# SOC_nRF52832.net
KiCad netlist of a schematic drawn in Altium Designer
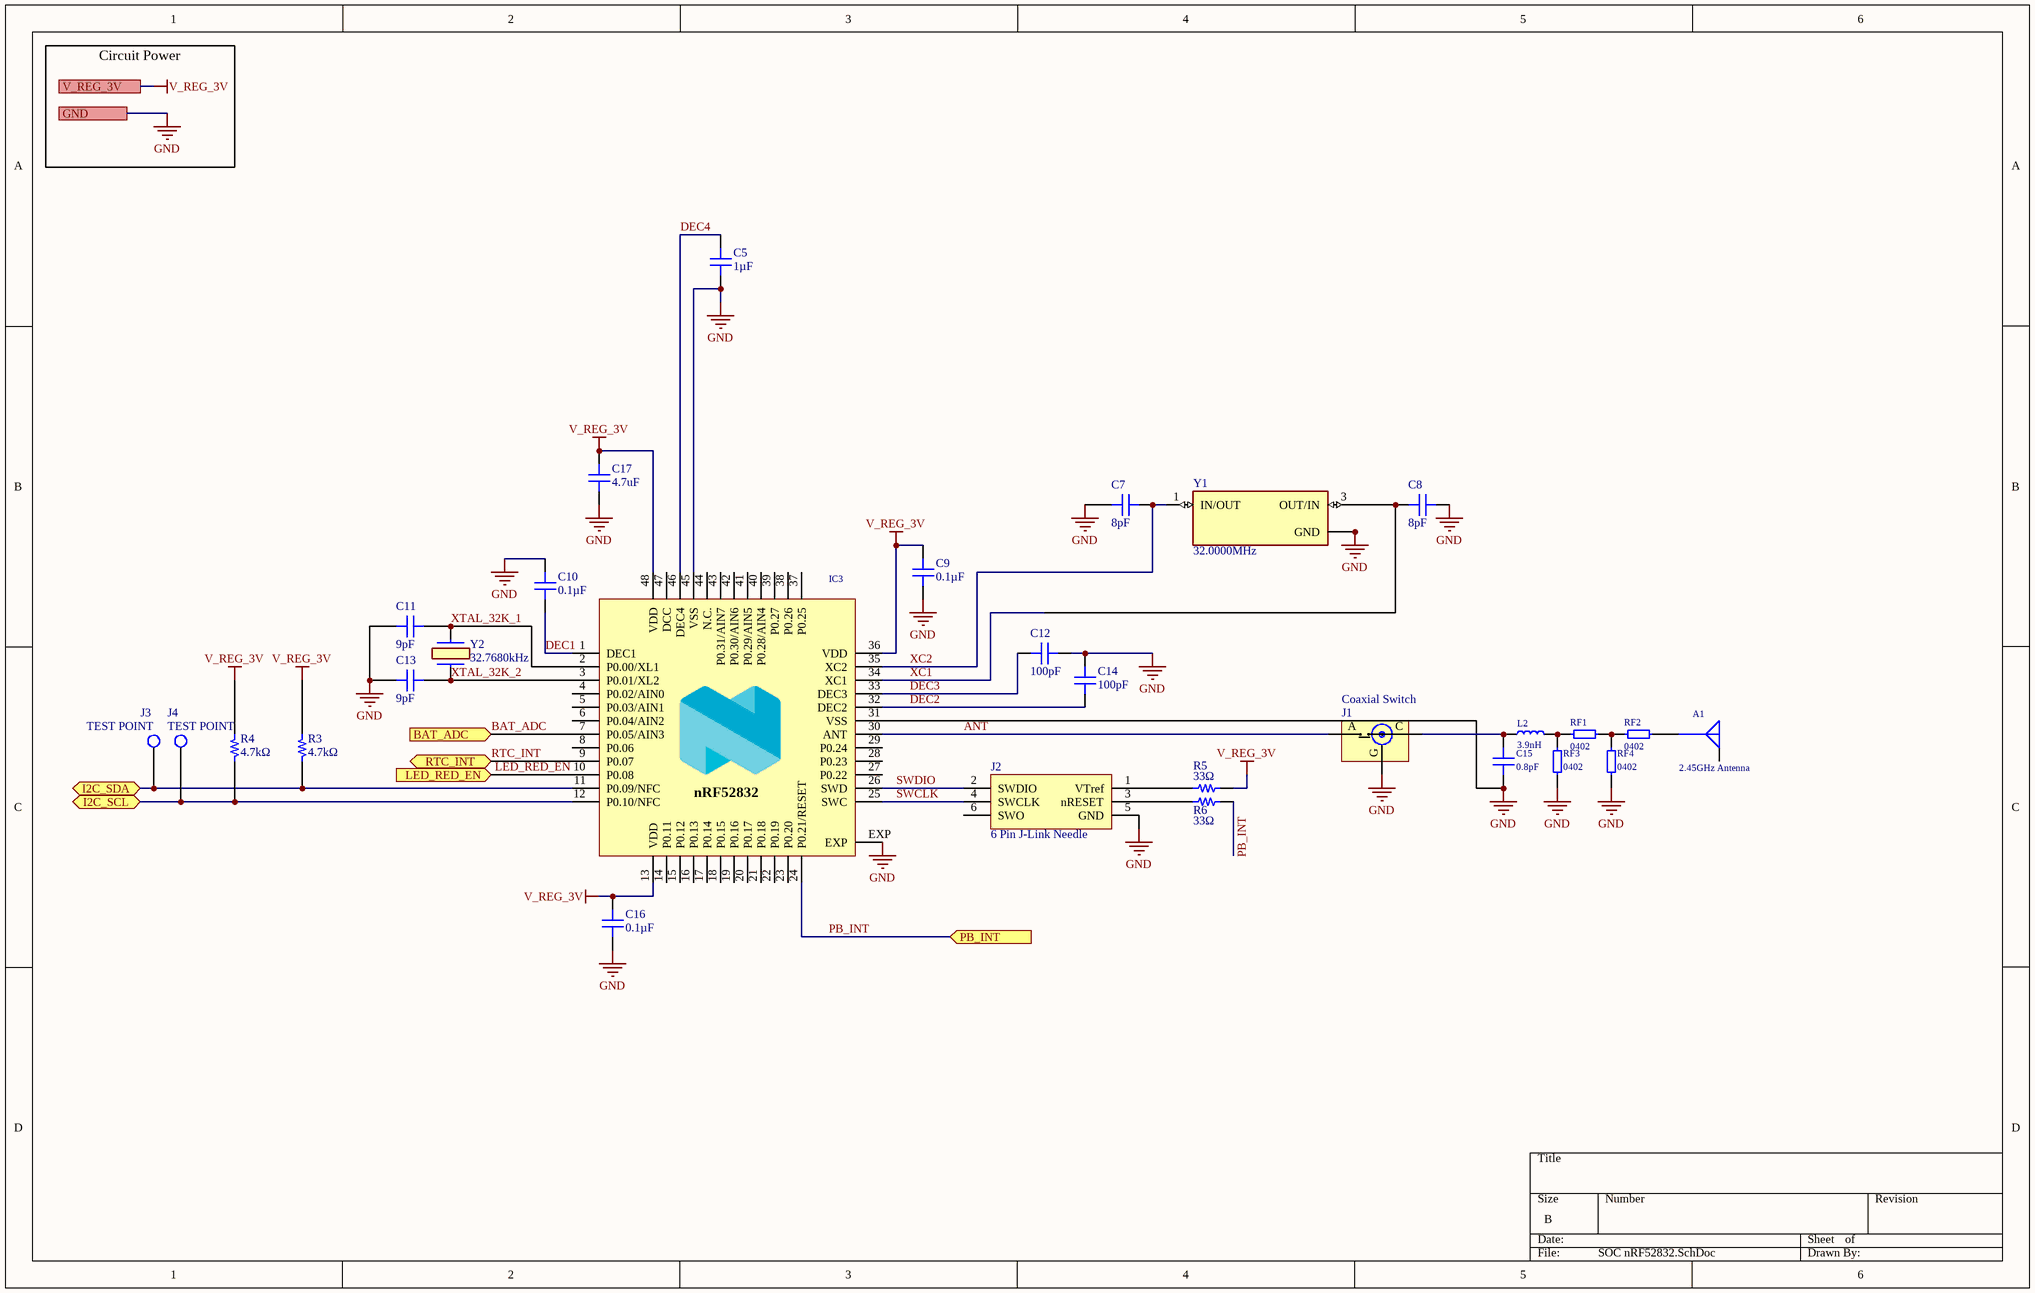
[diagram p0: SOC nRF52832.SchDoc]

(export (version "E")
  (design (tool "Eeschema 10.0.6"))
  (components
    (comp (ref "A1")
      (value "2.45GHz Antenna")
      (footprint "FRACTUS ANTENNAS FR01-S1-N-0-102")
      (description "COMPACT REACH XTEND - 102")
      (fields (field (name "MANUFACTURER") "Ignion"))
      (libsource (lib "MVVVMAltiumDatabase") (part "Basic Antenna"))
    )
    (comp (ref "C5")
      (value "1µF")
      (footprint "CAP 0402_1005 RF")
      (description "CAP CER 1UF 10V X7S 0402")
      (fields (field (name "MANUFACTURER") "Murata Electronics") (field (name "VOLTAGE") "10V"))
      (libsource (lib "MVVVMAltiumDatabase") (part "Capacitor"))
    )
    (comp (ref "C7")
      (value "8pF")
      (footprint "CAP 0402_1005")
      (description "CAP CER 8PF 50V NPO 0402")
      (fields (field (name "MANUFACTURER") "Walsin") (field (name "VOLTAGE") "50V"))
      (libsource (lib "MVVVMAltiumDatabase") (part "Capacitor"))
    )
    (comp (ref "C8")
      (value "8pF")
      (footprint "CAP 0402_1005")
      (description "CAP CER 8PF 50V NPO 0402")
      (fields (field (name "MANUFACTURER") "Walsin") (field (name "VOLTAGE") "50V"))
      (libsource (lib "MVVVMAltiumDatabase") (part "Capacitor"))
    )
    (comp (ref "C9")
      (value "0.1µF")
      (footprint "CAP 0402_1005")
      (description "CAP CER 0.1UF 16V X7R 0402")
      (fields (field (name "MANUFACTURER") "KEMET") (field (name "VOLTAGE") "16V"))
      (libsource (lib "MVVVMAltiumDatabase") (part "Capacitor"))
    )
    (comp (ref "C10")
      (value "0.1µF")
      (footprint "CAP 0402_1005")
      (description "CAP CER 0.1UF 16V X7R 0402")
      (fields (field (name "MANUFACTURER") "KEMET") (field (name "VOLTAGE") "16V"))
      (libsource (lib "MVVVMAltiumDatabase") (part "Capacitor"))
    )
    (comp (ref "C11")
      (value "9pF")
      (footprint "CAP 0402_1005")
      (description "CAP CER 9PF 50V NPO 0402")
      (fields (field (name "MANUFACTURER") "Walsin") (field (name "VOLTAGE") "50V"))
      (libsource (lib "MVVVMAltiumDatabase") (part "Capacitor"))
    )
    (comp (ref "C12")
      (value "100pF")
      (footprint "CAP 0402_1005")
      (description "CAP CER 100PF 16V C0G/NP0 0402")
      (fields (field (name "MANUFACTURER") "KEMET") (field (name "VOLTAGE") "16V"))
      (libsource (lib "MVVVMAltiumDatabase") (part "Capacitor"))
    )
    (comp (ref "C13")
      (value "9pF")
      (footprint "CAP 0402_1005")
      (description "CAP CER 9PF 50V NPO 0402")
      (fields (field (name "MANUFACTURER") "Walsin") (field (name "VOLTAGE") "50V"))
      (libsource (lib "MVVVMAltiumDatabase") (part "Capacitor"))
    )
    (comp (ref "C14")
      (value "100pF")
      (footprint "CAP 0402_1005")
      (description "CAP CER 100PF 16V C0G/NP0 0402")
      (fields (field (name "MANUFACTURER") "KEMET") (field (name "VOLTAGE") "16V"))
      (libsource (lib "MVVVMAltiumDatabase") (part "Capacitor"))
    )
    (comp (ref "C15")
      (value "0.8pF")
      (footprint "CAP 0603_1608")
      (description "CAP CER 0.8PF 50V NP0  0603")
      (fields (field (name "MANUFACTURER") "Walsin") (field (name "VOLTAGE") "50V"))
      (libsource (lib "MVVVMAltiumDatabase") (part "Capacitor"))
    )
    (comp (ref "C16")
      (value "0.1µF")
      (footprint "CAP 0402_1005")
      (description "CAP CER 0.1UF 16V X7R 0402")
      (fields (field (name "MANUFACTURER") "KEMET") (field (name "VOLTAGE") "16V"))
      (libsource (lib "MVVVMAltiumDatabase") (part "Capacitor"))
    )
    (comp (ref "C17")
      (value "4.7uF")
      (footprint "CAP 0402_1005")
      (description "CAP CER 8PF 50V NPO 0402")
      (fields (field (name "MANUFACTURER") "Samsung Electro-Mechanics") (field (name "VOLTAGE") "10V"))
      (libsource (lib "MVVVMAltiumDatabase") (part "Capacitor"))
    )
    (comp (ref "IC3")
      (value "RF SoC")
      (footprint "NORDIC QFN-48")
      (description "IC RF TXRX+MCU BLUETOOTH 48VFQFN")
      (fields (field (name "MANUFACTURER") "Nordic Semiconductor"))
      (libsource (lib "MVVVMAltiumDatabase") (part "NORDIC NRF52832 QFN48"))
    )
    (comp (ref "J1")
      (value "Coaxial Switch")
      (footprint "HIROSE MS-156HF(01)")
      (description "CONN COAX SWITCH RCPT STR 50OHM")
      (fields (field (name "MANUFACTURER") "Hirose Electric Co Ltd"))
      (libsource (lib "MVVVMAltiumDatabase") (part "HIROSE MS-156HF(01)"))
    )
    (comp (ref "J2")
      (value "6 Pin J-Link Needle")
      (footprint "J-LINK 6-PIN NEEDLE")
      (libsource (lib "MVVVMAltiumDatabase") (part "6 Pin"))
    )
    (comp (ref "J3")
      (value "TEST POINT")
      (footprint "TEST POINT")
      (libsource (lib "MVVVMAltiumDatabase") (part "TEST POINT"))
    )
    (comp (ref "J4")
      (value "TEST POINT")
      (footprint "TEST POINT")
      (libsource (lib "MVVVMAltiumDatabase") (part "TEST POINT"))
    )
    (comp (ref "L2")
      (value "3.9nH")
      (footprint "IND 0402_1005")
      (description "FIXED IND 3.9NH 250MA 450MOHM SM")
      (fields (field (name "MANUFACTURER") "KYOCERA AVX") (field (name "TOLERANCE") "±0.1%"))
      (libsource (lib "MVVVMAltiumDatabase") (part "Inductor_2"))
    )
    (comp (ref "R3")
      (value "4.7kΩ")
      (footprint "RES 0402_1005 RF")
      (description "RES SMD 4.7K OHM 1% 1/8W 0402")
      (fields (field (name "MANUFACTURER") "YAGEO") (field (name "TOLERANCE") "±1%"))
      (libsource (lib "MVVVMAltiumDatabase") (part "Resistor"))
    )
    (comp (ref "R4")
      (value "4.7kΩ")
      (footprint "RES 0402_1005 RF")
      (description "RES SMD 4.7K OHM 1% 1/8W 0402")
      (fields (field (name "MANUFACTURER") "YAGEO") (field (name "TOLERANCE") "±1%"))
      (libsource (lib "MVVVMAltiumDatabase") (part "Resistor"))
    )
    (comp (ref "R5")
      (value "33Ω")
      (footprint "RES 0201_0603")
      (description "RES SMD 33 OHM 1% 1/20W 0201")
      (fields (field (name "MANUFACTURER") "Vishay Dale") (field (name "TOLERANCE") "±1%"))
      (libsource (lib "MVVVMAltiumDatabase") (part "Resistor"))
    )
    (comp (ref "R6")
      (value "33Ω")
      (footprint "RES 0201_0603")
      (description "RES SMD 33 OHM 1% 1/20W 0201")
      (fields (field (name "MANUFACTURER") "Vishay Dale") (field (name "TOLERANCE") "±1%"))
      (libsource (lib "MVVVMAltiumDatabase") (part "Resistor"))
    )
    (comp (ref "RF1")
      (value "0402")
      (footprint "0402_1005 RF")
      (description "0402 RF Passive")
      (libsource (lib "MVVVMAltiumDatabase") (part "RF Passive"))
    )
    (comp (ref "RF2")
      (value "0402")
      (footprint "0402_1005 RF")
      (description "0402 RF Passive")
      (libsource (lib "MVVVMAltiumDatabase") (part "RF Passive"))
    )
    (comp (ref "RF3")
      (value "0402")
      (footprint "0402_1005 RF")
      (description "0402 RF Passive")
      (libsource (lib "MVVVMAltiumDatabase") (part "RF Passive"))
    )
    (comp (ref "RF4")
      (value "0402")
      (footprint "0402_1005 RF")
      (description "0402 RF Passive")
      (libsource (lib "MVVVMAltiumDatabase") (part "RF Passive"))
    )
    (comp (ref "Y1")
      (value "32.0000MHz")
      (footprint "ECS 320-8-37B")
      (description "CRYSTAL 32.0000MHZ 8PF SMD")
      (fields (field (name "MANUFACTURER") "ECS") (field (name "TOLERANCE") "±7ppm"))
      (libsource (lib "MVVVMAltiumDatabase") (part "ECS CRYSTAL 320-8-37B"))
    )
    (comp (ref "Y2")
      (value "32.7680kHz")
      (footprint "EPSON FC135R")
      (description "CRYSTAL 32.7680KHZ 9PF SMD")
      (fields (field (name "MANUFACTURER") "EPSON") (field (name "TOLERANCE") "±10ppm"))
      (libsource (lib "MVVVMAltiumDatabase") (part "EPSON CRYSTAL FC135R"))
    )
  )
  (nets
    (net (code "1") (name "/ANT") (class "Default")
      (node (ref "IC3") (pin "30") (pinfunction "ANT_30") (pintype "passive"))
      (node (ref "J1") (pin "A") (pinfunction "A_A") (pintype "passive"))
    )
    (net (code "2") (name "/BAT_ADC") (class "Default")
      (node (ref "IC3") (pin "7") (pinfunction "P0.05/AIN3_7") (pintype "passive"))
    )
    (net (code "3") (name "/DEC1") (class "Default")
      (node (ref "C10") (pin "1") (pinfunction "1_1") (pintype "passive"))
      (node (ref "IC3") (pin "1") (pinfunction "DEC1_1") (pintype "passive"))
    )
    (net (code "4") (name "/DEC2") (class "Default")
      (node (ref "C14") (pin "1") (pinfunction "1_1") (pintype "passive"))
      (node (ref "IC3") (pin "32") (pinfunction "DEC2_32") (pintype "passive"))
    )
    (net (code "5") (name "/DEC3") (class "Default")
      (node (ref "C12") (pin "1") (pinfunction "1_1") (pintype "passive"))
      (node (ref "IC3") (pin "33") (pinfunction "DEC3_33") (pintype "passive"))
    )
    (net (code "6") (name "/DEC4") (class "Default")
      (node (ref "C5") (pin "2") (pinfunction "2_2") (pintype "passive"))
      (node (ref "IC3") (pin "46") (pinfunction "DEC4_46") (pintype "passive"))
    )
    (net (code "7") (name "/I2C_SCL") (class "Default")
      (node (ref "IC3") (pin "12") (pinfunction "P0.10/NFC_12") (pintype "passive"))
      (node (ref "J4") (pin "1") (pinfunction "PAD_1") (pintype "passive"))
      (node (ref "R4") (pin "1") (pinfunction "1_1") (pintype "passive"))
    )
    (net (code "8") (name "/I2C_SDA") (class "Default")
      (node (ref "IC3") (pin "11") (pinfunction "P0.09/NFC_11") (pintype "passive"))
      (node (ref "J3") (pin "1") (pinfunction "PAD_1") (pintype "passive"))
      (node (ref "R3") (pin "1") (pinfunction "1_1") (pintype "passive"))
    )
    (net (code "9") (name "/LED_RED_EN") (class "Default")
      (node (ref "IC3") (pin "10") (pinfunction "P0.08_10") (pintype "passive"))
    )
    (net (code "10") (name "/PB_INT") (class "Default")
      (node (ref "IC3") (pin "24") (pinfunction "P0.21/RESET_24") (pintype "passive"))
      (node (ref "R6") (pin "2") (pinfunction "2_2") (pintype "passive"))
    )
    (net (code "11") (name "/RTC_INT") (class "Default")
      (node (ref "IC3") (pin "9") (pinfunction "P0.07_9") (pintype "passive"))
    )
    (net (code "12") (name "/SWCLK") (class "Default")
      (node (ref "IC3") (pin "25") (pinfunction "SWC_25") (pintype "passive"))
      (node (ref "J2") (pin "4") (pinfunction "SWCLK_4") (pintype "passive"))
    )
    (net (code "13") (name "/SWDIO") (class "Default")
      (node (ref "IC3") (pin "26") (pinfunction "SWD_26") (pintype "passive"))
      (node (ref "J2") (pin "2") (pinfunction "SWDIO_2") (pintype "passive"))
    )
    (net (code "14") (name "/XC1") (class "Default")
      (node (ref "C8") (pin "1") (pinfunction "1_1") (pintype "passive"))
      (node (ref "IC3") (pin "34") (pinfunction "XC1_34") (pintype "passive"))
      (node (ref "Y1") (pin "3") (pinfunction "OUT/IN_3") (pintype "bidirectional"))
    )
    (net (code "15") (name "/XC2") (class "Default")
      (node (ref "C7") (pin "2") (pinfunction "2_2") (pintype "passive"))
      (node (ref "IC3") (pin "35") (pinfunction "XC2_35") (pintype "passive"))
      (node (ref "Y1") (pin "1") (pinfunction "IN/OUT_1") (pintype "bidirectional"))
    )
    (net (code "16") (name "/XTAL_32K_1") (class "Default")
      (node (ref "C11") (pin "2") (pinfunction "2_2") (pintype "passive"))
      (node (ref "IC3") (pin "2") (pinfunction "P0.00/XL1_2") (pintype "passive"))
      (node (ref "Y2") (pin "1") (pinfunction "CRYSTAL_1_1") (pintype "passive"))
    )
    (net (code "17") (name "/XTAL_32K_2") (class "Default")
      (node (ref "C13") (pin "2") (pinfunction "2_2") (pintype "passive"))
      (node (ref "IC3") (pin "3") (pinfunction "P0.01/XL2_3") (pintype "passive"))
      (node (ref "Y2") (pin "2") (pinfunction "CRYSTAL_2_2") (pintype "passive"))
    )
    (net (code "18") (name "GND") (class "Default")
      (node (ref "C10") (pin "2") (pinfunction "2_2") (pintype "passive"))
      (node (ref "C11") (pin "1") (pinfunction "1_1") (pintype "passive"))
      (node (ref "C12") (pin "2") (pinfunction "2_2") (pintype "passive"))
      (node (ref "C13") (pin "1") (pinfunction "1_1") (pintype "passive"))
      (node (ref "C14") (pin "2") (pinfunction "2_2") (pintype "passive"))
      (node (ref "C15") (pin "1") (pinfunction "1_1") (pintype "passive"))
      (node (ref "C16") (pin "1") (pinfunction "1_1") (pintype "passive"))
      (node (ref "C17") (pin "1") (pinfunction "1_1") (pintype "passive"))
      (node (ref "C5") (pin "1") (pinfunction "1_1") (pintype "passive"))
      (node (ref "C7") (pin "1") (pinfunction "1_1") (pintype "passive"))
      (node (ref "C8") (pin "2") (pinfunction "2_2") (pintype "passive"))
      (node (ref "C9") (pin "1") (pinfunction "1_1") (pintype "passive"))
      (node (ref "IC3") (pin "31") (pinfunction "VSS_31") (pintype "passive"))
      (node (ref "IC3") (pin "45") (pinfunction "VSS_45") (pintype "passive"))
      (node (ref "IC3") (pin "EXP") (pinfunction "EXP_EXP") (pintype "passive"))
      (node (ref "J1") (pin "G") (pinfunction "G_G") (pintype "passive"))
      (node (ref "J2") (pin "5") (pinfunction "GND_5") (pintype "passive"))
      (node (ref "RF3") (pin "1") (pinfunction "1_1") (pintype "passive"))
      (node (ref "RF4") (pin "1") (pinfunction "1_1") (pintype "passive"))
      (node (ref "Y1") (pin "2") (pinfunction "GND_2") (pintype "power_in"))
      (node (ref "Y1") (pin "4") (pinfunction "GND_4") (pintype "power_in"))
    )
    (net (code "19") (name "Net-(A1-PadS)") (class "Default")
      (node (ref "A1") (pin "S") (pinfunction "S_S") (pintype "passive"))
      (node (ref "RF2") (pin "2") (pinfunction "2_2") (pintype "passive"))
    )
    (net (code "20") (name "Net-(C15-Pad2)") (class "Default")
      (node (ref "C15") (pin "2") (pinfunction "2_2") (pintype "passive"))
      (node (ref "J1") (pin "C") (pinfunction "C_C") (pintype "passive"))
      (node (ref "L2") (pin "1") (pinfunction "1_1") (pintype "passive"))
    )
    (net (code "21") (name "Net-(J2-VTref)") (class "Default")
      (node (ref "J2") (pin "1") (pinfunction "VTref_1") (pintype "passive"))
      (node (ref "R5") (pin "1") (pinfunction "1_1") (pintype "passive"))
    )
    (net (code "22") (name "Net-(J2-nRESET)") (class "Default")
      (node (ref "J2") (pin "3") (pinfunction "nRESET_3") (pintype "passive"))
      (node (ref "R6") (pin "1") (pinfunction "1_1") (pintype "passive"))
    )
    (net (code "23") (name "Net-(L2-Pad2)") (class "Default")
      (node (ref "L2") (pin "2") (pinfunction "2_2") (pintype "passive"))
      (node (ref "RF1") (pin "1") (pinfunction "1_1") (pintype "passive"))
      (node (ref "RF3") (pin "2") (pinfunction "2_2") (pintype "passive"))
    )
    (net (code "24") (name "Net-(RF1-Pad2)") (class "Default")
      (node (ref "RF1") (pin "2") (pinfunction "2_2") (pintype "passive"))
      (node (ref "RF2") (pin "1") (pinfunction "1_1") (pintype "passive"))
      (node (ref "RF4") (pin "2") (pinfunction "2_2") (pintype "passive"))
    )
    (net (code "25") (name "V_REG_3V") (class "Default")
      (node (ref "C16") (pin "2") (pinfunction "2_2") (pintype "passive"))
      (node (ref "C17") (pin "2") (pinfunction "2_2") (pintype "passive"))
      (node (ref "C9") (pin "2") (pinfunction "2_2") (pintype "passive"))
      (node (ref "IC3") (pin "13") (pinfunction "VDD_13") (pintype "passive"))
      (node (ref "IC3") (pin "36") (pinfunction "VDD_36") (pintype "passive"))
      (node (ref "IC3") (pin "48") (pinfunction "VDD_48") (pintype "passive"))
      (node (ref "R3") (pin "2") (pinfunction "2_2") (pintype "passive"))
      (node (ref "R4") (pin "2") (pinfunction "2_2") (pintype "passive"))
      (node (ref "R5") (pin "2") (pinfunction "2_2") (pintype "passive"))
    )
    (net (code "26") (name "unconnected-(A1-PadG)") (class "Default")
      (node (ref "A1") (pin "G") (pinfunction "G_G") (pintype "passive"))
    )
    (net (code "27") (name "unconnected-(IC3-DCC-Pad47)") (class "Default")
      (node (ref "IC3") (pin "47") (pinfunction "DCC_47") (pintype "passive"))
    )
    (net (code "28") (name "unconnected-(IC3-N.C.-Pad44)") (class "Default")
      (node (ref "IC3") (pin "44") (pinfunction "N.C._44") (pintype "passive"))
    )
    (net (code "29") (name "unconnected-(IC3-P0.02{slash}AIN0-Pad4)") (class "Default")
      (node (ref "IC3") (pin "4") (pinfunction "P0.02/AIN0_4") (pintype "passive"))
    )
    (net (code "30") (name "unconnected-(IC3-P0.03{slash}AIN1-Pad5)") (class "Default")
      (node (ref "IC3") (pin "5") (pinfunction "P0.03/AIN1_5") (pintype "passive"))
    )
    (net (code "31") (name "unconnected-(IC3-P0.04{slash}AIN2-Pad6)") (class "Default")
      (node (ref "IC3") (pin "6") (pinfunction "P0.04/AIN2_6") (pintype "passive"))
    )
    (net (code "32") (name "unconnected-(IC3-P0.06-Pad8)") (class "Default")
      (node (ref "IC3") (pin "8") (pinfunction "P0.06_8") (pintype "passive"))
    )
    (net (code "33") (name "unconnected-(IC3-P0.11-Pad14)") (class "Default")
      (node (ref "IC3") (pin "14") (pinfunction "P0.11_14") (pintype "passive"))
    )
    (net (code "34") (name "unconnected-(IC3-P0.12-Pad15)") (class "Default")
      (node (ref "IC3") (pin "15") (pinfunction "P0.12_15") (pintype "passive"))
    )
    (net (code "35") (name "unconnected-(IC3-P0.13-Pad16)") (class "Default")
      (node (ref "IC3") (pin "16") (pinfunction "P0.13_16") (pintype "passive"))
    )
    (net (code "36") (name "unconnected-(IC3-P0.14-Pad17)") (class "Default")
      (node (ref "IC3") (pin "17") (pinfunction "P0.14_17") (pintype "passive"))
    )
    (net (code "37") (name "unconnected-(IC3-P0.15-Pad18)") (class "Default")
      (node (ref "IC3") (pin "18") (pinfunction "P0.15_18") (pintype "passive"))
    )
    (net (code "38") (name "unconnected-(IC3-P0.16-Pad19)") (class "Default")
      (node (ref "IC3") (pin "19") (pinfunction "P0.16_19") (pintype "passive"))
    )
    (net (code "39") (name "unconnected-(IC3-P0.17-Pad20)") (class "Default")
      (node (ref "IC3") (pin "20") (pinfunction "P0.17_20") (pintype "passive"))
    )
    (net (code "40") (name "unconnected-(IC3-P0.18-Pad21)") (class "Default")
      (node (ref "IC3") (pin "21") (pinfunction "P0.18_21") (pintype "passive"))
    )
    (net (code "41") (name "unconnected-(IC3-P0.19-Pad22)") (class "Default")
      (node (ref "IC3") (pin "22") (pinfunction "P0.19_22") (pintype "passive"))
    )
    (net (code "42") (name "unconnected-(IC3-P0.20-Pad23)") (class "Default")
      (node (ref "IC3") (pin "23") (pinfunction "P0.20_23") (pintype "passive"))
    )
    (net (code "43") (name "unconnected-(IC3-P0.22-Pad27)") (class "Default")
      (node (ref "IC3") (pin "27") (pinfunction "P0.22_27") (pintype "passive"))
    )
    (net (code "44") (name "unconnected-(IC3-P0.23-Pad28)") (class "Default")
      (node (ref "IC3") (pin "28") (pinfunction "P0.23_28") (pintype "passive"))
    )
    (net (code "45") (name "unconnected-(IC3-P0.24-Pad29)") (class "Default")
      (node (ref "IC3") (pin "29") (pinfunction "P0.24_29") (pintype "passive"))
    )
    (net (code "46") (name "unconnected-(IC3-P0.25-Pad37)") (class "Default")
      (node (ref "IC3") (pin "37") (pinfunction "P0.25_37") (pintype "passive"))
    )
    (net (code "47") (name "unconnected-(IC3-P0.26-Pad38)") (class "Default")
      (node (ref "IC3") (pin "38") (pinfunction "P0.26_38") (pintype "passive"))
    )
    (net (code "48") (name "unconnected-(IC3-P0.27-Pad39)") (class "Default")
      (node (ref "IC3") (pin "39") (pinfunction "P0.27_39") (pintype "passive"))
    )
    (net (code "49") (name "unconnected-(IC3-P0.28{slash}AIN4-Pad40)") (class "Default")
      (node (ref "IC3") (pin "40") (pinfunction "P0.28/AIN4_40") (pintype "passive"))
    )
    (net (code "50") (name "unconnected-(IC3-P0.29{slash}AIN5-Pad41)") (class "Default")
      (node (ref "IC3") (pin "41") (pinfunction "P0.29/AIN5_41") (pintype "passive"))
    )
    (net (code "51") (name "unconnected-(IC3-P0.30{slash}AIN6-Pad42)") (class "Default")
      (node (ref "IC3") (pin "42") (pinfunction "P0.30/AIN6_42") (pintype "passive"))
    )
    (net (code "52") (name "unconnected-(IC3-P0.31{slash}AIN7-Pad43)") (class "Default")
      (node (ref "IC3") (pin "43") (pinfunction "P0.31/AIN7_43") (pintype "passive"))
    )
    (net (code "53") (name "unconnected-(J2-SWO-Pad6)") (class "Default")
      (node (ref "J2") (pin "6") (pinfunction "SWO_6") (pintype "passive"))
    )
  )
)
